# DMX-Controller.net
KiCad netlist of a schematic drawn in EAGLE
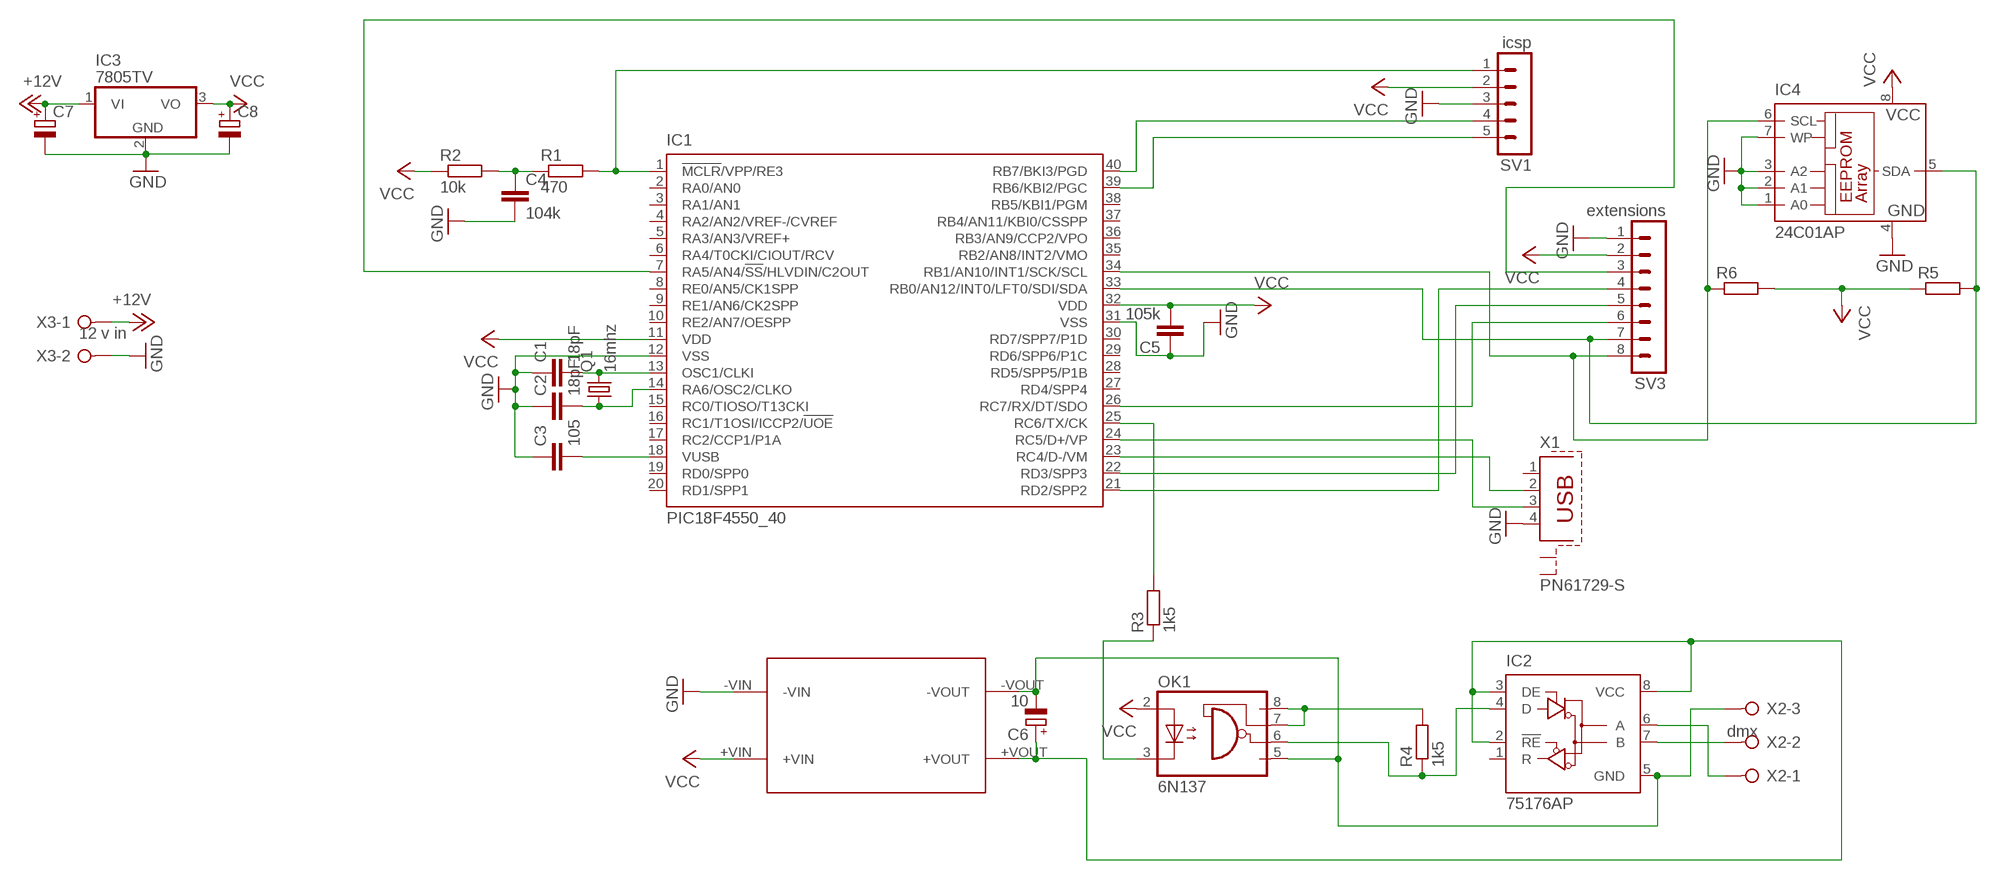
[diagram p0: schematic, sheet 1]

(export (version "E")
  (design (tool "Eeschema 10.0.6"))
  (components
    (comp (ref "C1")
      (value "18pF")
      (footprint "eagle-import:C050-024X044")
      (libsource (lib "eagle-import") (part "C-EU050-024X044"))
    )
    (comp (ref "C2")
      (value "18pF")
      (footprint "eagle-import:C050-024X044")
      (libsource (lib "eagle-import") (part "C-EU050-024X044"))
    )
    (comp (ref "C3")
      (value "105")
      (footprint "eagle-import:C050-024X044")
      (libsource (lib "eagle-import") (part "C-EU050-024X044"))
    )
    (comp (ref "C4")
      (value "104k")
      (footprint "eagle-import:C050-024X044")
      (libsource (lib "eagle-import") (part "C-EU050-024X044"))
    )
    (comp (ref "C5")
      (value "105k")
      (footprint "eagle-import:C050-024X044")
      (libsource (lib "eagle-import") (part "C-EU050-024X044"))
    )
    (comp (ref "C6")
      (value "10")
      (footprint "eagle-import:E2,5-6")
      (libsource (lib "eagle-import") (part "CPOL-EUE2.5-6"))
    )
    (comp (ref "C7")
      (value "CPOL-EUE2.5-6")
      (footprint "eagle-import:E2,5-6")
      (libsource (lib "eagle-import") (part "CPOL-EUE2.5-6"))
    )
    (comp (ref "C8")
      (value "CPOL-EUE2.5-6")
      (footprint "eagle-import:E2,5-6")
      (libsource (lib "eagle-import") (part "CPOL-EUE2.5-6"))
    )
    (comp (ref "IC1")
      (value "PIC18F4550_40")
      (footprint "eagle-import:DIL40")
      (fields (field (name "MF") "MICROCHIP") (field (name "MPN") "PIC18F4550-I/P"))
      (libsource (lib "eagle-import") (part "PIC18F4_40550"))
    )
    (comp (ref "IC2")
      (value "75176AP")
      (footprint "eagle-import:DIL08")
      (libsource (lib "eagle-import") (part "75176AP"))
    )
    (comp (ref "IC3")
      (value "7805TV")
      (footprint "eagle-import:TO220V")
      (libsource (lib "eagle-import") (part "78TV05"))
    )
    (comp (ref "IC4")
      (value "24C01AP")
      (footprint "eagle-import:DIL8")
      (fields (field (name "MF") "Arrow Electronics") (field (name "MPN") "M24C01-WBN6P"))
      (libsource (lib "eagle-import") (part "24CP01A"))
    )
    (comp (ref "OK1")
      (value "6N137")
      (footprint "eagle-import:DIL08")
      (libsource (lib "eagle-import") (part "6N137"))
    )
    (comp (ref "Q1")
      (value "16mhz")
      (footprint "eagle-import:HC49U-V")
      (libsource (lib "eagle-import") (part "CRYSTALHC49U-V"))
    )
    (comp (ref "R1")
      (value "470")
      (footprint "eagle-import:0207_10")
      (libsource (lib "eagle-import") (part "R-EU_0207/10"))
    )
    (comp (ref "R2")
      (value "10k")
      (footprint "eagle-import:0207_10")
      (libsource (lib "eagle-import") (part "R-EU_0207/10"))
    )
    (comp (ref "R3")
      (value "1k5")
      (footprint "eagle-import:0207_10")
      (libsource (lib "eagle-import") (part "R-EU_0207/10"))
    )
    (comp (ref "R4")
      (value "1k5")
      (footprint "eagle-import:0207_10")
      (libsource (lib "eagle-import") (part "R-EU_0207/10"))
    )
    (comp (ref "R5")
      (value "R-EU_0207/10")
      (footprint "eagle-import:0207_10")
      (libsource (lib "eagle-import") (part "R-EU_0207/10"))
    )
    (comp (ref "R6")
      (value "R-EU_0207/10")
      (footprint "eagle-import:0207_10")
      (libsource (lib "eagle-import") (part "R-EU_0207/10"))
    )
    (comp (ref "SV1")
      (value "icsp")
      (footprint "eagle-import:MA05-1")
      (libsource (lib "eagle-import") (part "MA05-1"))
    )
    (comp (ref "SV3")
      (value "extensions")
      (footprint "eagle-import:MA08-1")
      (libsource (lib "eagle-import") (part "MA08-1"))
    )
    (comp (ref "U$1")
      (value "SIM1-0505SZ")
      (footprint "eagle-import:SIM-0505SZ")
      (libsource (lib "eagle-import") (part "SIM1-0505SZ"))
    )
    (comp (ref "X1")
      (value "PN61729-S")
      (footprint "eagle-import:PN61729-S")
      (libsource (lib "eagle-import") (part "PN61729-S"))
    )
    (comp (ref "X2")
      (value "dmx")
      (footprint "eagle-import:W237-3E")
      (libsource (lib "eagle-import") (part "W237-3E"))
    )
    (comp (ref "X3")
      (value "12 v in")
      (footprint "eagle-import:W237-132")
      (libsource (lib "eagle-import") (part "W237-02P"))
    )
  )
  (nets
    (net (code "1") (name "+12V") (class "Default")
      (node (ref "C7") (pin "+") (pinfunction "+_+") (pintype "passive"))
      (node (ref "IC3") (pin "1") (pinfunction "VI_1") (pintype "input"))
      (node (ref "X3") (pin "1") (pinfunction "KL_1") (pintype "passive"))
    )
    (net (code "2") (name "GND") (class "Default")
      (node (ref "C1") (pin "1") (pinfunction "1_1") (pintype "passive"))
      (node (ref "C2") (pin "1") (pinfunction "1_1") (pintype "passive"))
      (node (ref "C3") (pin "1") (pinfunction "1_1") (pintype "passive"))
      (node (ref "C4") (pin "2") (pinfunction "2_2") (pintype "passive"))
      (node (ref "C5") (pin "1") (pinfunction "1_1") (pintype "passive"))
      (node (ref "C7") (pin "-") (pinfunction "-_-") (pintype "passive"))
      (node (ref "C8") (pin "-") (pinfunction "-_-") (pintype "passive"))
      (node (ref "IC1") (pin "12") (pinfunction "VSS_12") (pintype "power_in"))
      (node (ref "IC1") (pin "31") (pinfunction "VSS_31") (pintype "power_in"))
      (node (ref "IC3") (pin "2") (pinfunction "GND_2") (pintype "passive"))
      (node (ref "IC4") (pin "1") (pinfunction "A0_1") (pintype "input"))
      (node (ref "IC4") (pin "2") (pinfunction "A1_2") (pintype "input"))
      (node (ref "IC4") (pin "3") (pinfunction "A2_3") (pintype "input"))
      (node (ref "IC4") (pin "4") (pinfunction "GND_4") (pintype "power_in"))
      (node (ref "IC4") (pin "7") (pinfunction "WP_7") (pintype "input"))
      (node (ref "SV1") (pin "3") (pinfunction "3_3") (pintype "passive"))
      (node (ref "SV3") (pin "1") (pinfunction "1_1") (pintype "passive"))
      (node (ref "U$1") (pin "-VIN") (pinfunction "-VIN_-VIN") (pintype "input"))
      (node (ref "X1") (pin "4") (pinfunction "4_4") (pintype "passive"))
      (node (ref "X3") (pin "2") (pinfunction "KL_2") (pintype "passive"))
    )
    (net (code "3") (name "Net-(C4-Pad1)") (class "Default")
      (node (ref "C4") (pin "1") (pinfunction "1_1") (pintype "passive"))
      (node (ref "R1") (pin "1") (pinfunction "1_1") (pintype "passive"))
      (node (ref "R2") (pin "2") (pinfunction "2_2") (pintype "passive"))
    )
    (net (code "4") (name "Net-(IC1-OSC1{slash}CLKI)") (class "Default")
      (node (ref "C1") (pin "2") (pinfunction "2_2") (pintype "passive"))
      (node (ref "IC1") (pin "13") (pinfunction "OSC1/CLKI_13") (pintype "input"))
      (node (ref "Q1") (pin "2") (pinfunction "2_2") (pintype "passive"))
    )
    (net (code "5") (name "Net-(IC1-RA5{slash}AN4{slash}~{SS}{slash}HLVDIN{slash}C2OUT)") (class "Default")
      (node (ref "IC1") (pin "7") (pinfunction "RA5/AN4/~{SS}/HLVDIN/C2OUT_7") (pintype "bidirectional"))
      (node (ref "SV3") (pin "3") (pinfunction "3_3") (pintype "passive"))
    )
    (net (code "6") (name "Net-(IC1-RA6{slash}OSC2{slash}CLKO)") (class "Default")
      (node (ref "C2") (pin "2") (pinfunction "2_2") (pintype "passive"))
      (node (ref "IC1") (pin "14") (pinfunction "RA6/OSC2/CLKO_14") (pintype "output"))
      (node (ref "Q1") (pin "1") (pinfunction "1_1") (pintype "passive"))
    )
    (net (code "7") (name "Net-(IC1-RB0{slash}AN12{slash}INT0{slash}LFT0{slash}SDI{slash}SDA)") (class "Default")
      (node (ref "IC1") (pin "33") (pinfunction "RB0/AN12/INT0/LFT0/SDI/SDA_33") (pintype "bidirectional"))
      (node (ref "IC4") (pin "5") (pinfunction "SDA_5") (pintype "bidirectional"))
      (node (ref "R5") (pin "2") (pinfunction "2_2") (pintype "passive"))
      (node (ref "SV3") (pin "7") (pinfunction "7_7") (pintype "passive"))
    )
    (net (code "8") (name "Net-(IC1-RB1{slash}AN10{slash}INT1{slash}SCK{slash}SCL)") (class "Default")
      (node (ref "IC1") (pin "34") (pinfunction "RB1/AN10/INT1/SCK/SCL_34") (pintype "bidirectional"))
      (node (ref "IC4") (pin "6") (pinfunction "SCL_6") (pintype "input"))
      (node (ref "R6") (pin "1") (pinfunction "1_1") (pintype "passive"))
      (node (ref "SV3") (pin "8") (pinfunction "8_8") (pintype "passive"))
    )
    (net (code "9") (name "Net-(IC1-RB6{slash}KBI2{slash}PGC)") (class "Default")
      (node (ref "IC1") (pin "39") (pinfunction "RB6/KBI2/PGC_39") (pintype "bidirectional"))
      (node (ref "SV1") (pin "5") (pinfunction "5_5") (pintype "passive"))
    )
    (net (code "10") (name "Net-(IC1-RB7{slash}BKI3{slash}PGD)") (class "Default")
      (node (ref "IC1") (pin "40") (pinfunction "RB7/BKI3/PGD_40") (pintype "bidirectional"))
      (node (ref "SV1") (pin "4") (pinfunction "4_4") (pintype "passive"))
    )
    (net (code "11") (name "Net-(IC1-RC4{slash}D-{slash}VM)") (class "Default")
      (node (ref "IC1") (pin "23") (pinfunction "RC4/D-/VM_23") (pintype "bidirectional"))
      (node (ref "X1") (pin "2") (pinfunction "2_2") (pintype "passive"))
    )
    (net (code "12") (name "Net-(IC1-RC5{slash}D+{slash}VP)") (class "Default")
      (node (ref "IC1") (pin "24") (pinfunction "RC5/D+/VP_24") (pintype "bidirectional"))
      (node (ref "X1") (pin "3") (pinfunction "3_3") (pintype "passive"))
    )
    (net (code "13") (name "Net-(IC1-RC6{slash}TX{slash}CK)") (class "Default")
      (node (ref "IC1") (pin "25") (pinfunction "RC6/TX/CK_25") (pintype "bidirectional"))
      (node (ref "R3") (pin "2") (pinfunction "2_2") (pintype "passive"))
    )
    (net (code "14") (name "Net-(IC1-RC7{slash}RX{slash}DT{slash}SDO)") (class "Default")
      (node (ref "IC1") (pin "26") (pinfunction "RC7/RX/DT/SDO_26") (pintype "bidirectional"))
      (node (ref "SV3") (pin "6") (pinfunction "6_6") (pintype "passive"))
    )
    (net (code "15") (name "Net-(IC1-RD2{slash}SPP2)") (class "Default")
      (node (ref "IC1") (pin "21") (pinfunction "RD2/SPP2_21") (pintype "bidirectional"))
      (node (ref "SV3") (pin "4") (pinfunction "4_4") (pintype "passive"))
    )
    (net (code "16") (name "Net-(IC1-RD3{slash}SPP3)") (class "Default")
      (node (ref "IC1") (pin "22") (pinfunction "RD3/SPP3_22") (pintype "bidirectional"))
      (node (ref "SV3") (pin "5") (pinfunction "5_5") (pintype "passive"))
    )
    (net (code "17") (name "Net-(IC1-VUSB)") (class "Default")
      (node (ref "C3") (pin "2") (pinfunction "2_2") (pintype "passive"))
      (node (ref "IC1") (pin "18") (pinfunction "VUSB_18") (pintype "bidirectional"))
    )
    (net (code "18") (name "Net-(IC1-~{MCLR}{slash}VPP{slash}RE3)") (class "Default")
      (node (ref "IC1") (pin "1") (pinfunction "~{MCLR}/VPP/RE3_1") (pintype "input"))
      (node (ref "R1") (pin "2") (pinfunction "2_2") (pintype "passive"))
      (node (ref "SV1") (pin "1") (pinfunction "1_1") (pintype "passive"))
    )
    (net (code "19") (name "Net-(IC2-A)") (class "Default")
      (node (ref "IC2") (pin "6") (pinfunction "A_6") (pintype "output"))
      (node (ref "X2") (pin "1") (pinfunction "KL_1") (pintype "passive"))
    )
    (net (code "20") (name "Net-(IC2-B)") (class "Default")
      (node (ref "IC2") (pin "7") (pinfunction "B_7") (pintype "output"))
      (node (ref "X2") (pin "2") (pinfunction "KL_2") (pintype "passive"))
    )
    (net (code "21") (name "Net-(IC2-D)") (class "Default")
      (node (ref "IC2") (pin "4") (pinfunction "D_4") (pintype "input"))
      (node (ref "OK1") (pin "6") (pinfunction "VO_6") (pintype "passive"))
      (node (ref "R4") (pin "1") (pinfunction "1_1") (pintype "passive"))
    )
    (net (code "22") (name "Net-(IC2-DE)") (class "Default")
      (node (ref "C6") (pin "+") (pinfunction "+_+") (pintype "passive"))
      (node (ref "IC2") (pin "2") (pinfunction "~{RE}_2") (pintype "input"))
      (node (ref "IC2") (pin "3") (pinfunction "DE_3") (pintype "input"))
      (node (ref "IC2") (pin "8") (pinfunction "VCC_8") (pintype "power_in"))
      (node (ref "U$1") (pin "+VOUT") (pinfunction "+VOUT_+VOUT") (pintype "output"))
    )
    (net (code "23") (name "Net-(IC2-GND)") (class "Default")
      (node (ref "C6") (pin "-") (pinfunction "-_-") (pintype "passive"))
      (node (ref "IC2") (pin "5") (pinfunction "GND_5") (pintype "power_in"))
      (node (ref "OK1") (pin "5") (pinfunction "GND_5") (pintype "passive"))
      (node (ref "U$1") (pin "-VOUT") (pinfunction "-VOUT_-VOUT") (pintype "output"))
      (node (ref "X2") (pin "3") (pinfunction "KL_3") (pintype "passive"))
    )
    (net (code "24") (name "Net-(OK1-C)") (class "Default")
      (node (ref "OK1") (pin "3") (pinfunction "C_3") (pintype "passive"))
      (node (ref "R3") (pin "1") (pinfunction "1_1") (pintype "passive"))
    )
    (net (code "25") (name "Net-(OK1-VCC)") (class "Default")
      (node (ref "OK1") (pin "7") (pinfunction "VE_7") (pintype "passive"))
      (node (ref "OK1") (pin "8") (pinfunction "VCC_8") (pintype "passive"))
      (node (ref "R4") (pin "2") (pinfunction "2_2") (pintype "passive"))
    )
    (net (code "26") (name "VCC") (class "Default")
      (node (ref "C5") (pin "2") (pinfunction "2_2") (pintype "passive"))
      (node (ref "C8") (pin "+") (pinfunction "+_+") (pintype "passive"))
      (node (ref "IC1") (pin "11") (pinfunction "VDD_11") (pintype "power_in"))
      (node (ref "IC1") (pin "32") (pinfunction "VDD_32") (pintype "power_in"))
      (node (ref "IC3") (pin "3") (pinfunction "VO_3") (pintype "passive"))
      (node (ref "IC4") (pin "8") (pinfunction "VCC_8") (pintype "power_in"))
      (node (ref "OK1") (pin "2") (pinfunction "A_2") (pintype "passive"))
      (node (ref "R2") (pin "1") (pinfunction "1_1") (pintype "passive"))
      (node (ref "R5") (pin "1") (pinfunction "1_1") (pintype "passive"))
      (node (ref "R6") (pin "2") (pinfunction "2_2") (pintype "passive"))
      (node (ref "SV1") (pin "2") (pinfunction "2_2") (pintype "passive"))
      (node (ref "SV3") (pin "2") (pinfunction "2_2") (pintype "passive"))
      (node (ref "U$1") (pin "+VIN") (pinfunction "+VIN_+VIN") (pintype "input"))
    )
    (net (code "27") (name "unconnected-(IC1-RA0{slash}AN0-Pad2)") (class "Default")
      (node (ref "IC1") (pin "2") (pinfunction "RA0/AN0_2") (pintype "bidirectional"))
    )
    (net (code "28") (name "unconnected-(IC1-RA1{slash}AN1-Pad3)") (class "Default")
      (node (ref "IC1") (pin "3") (pinfunction "RA1/AN1_3") (pintype "bidirectional"))
    )
    (net (code "29") (name "unconnected-(IC1-RA2{slash}AN2{slash}VREF-{slash}CVREF-Pad4)") (class "Default")
      (node (ref "IC1") (pin "4") (pinfunction "RA2/AN2/VREF-/CVREF_4") (pintype "bidirectional"))
    )
    (net (code "30") (name "unconnected-(IC1-RA3{slash}AN3{slash}VREF+-Pad5)") (class "Default")
      (node (ref "IC1") (pin "5") (pinfunction "RA3/AN3/VREF+_5") (pintype "bidirectional"))
    )
    (net (code "31") (name "unconnected-(IC1-RA4{slash}T0CKI{slash}CIOUT{slash}RCV-Pad6)") (class "Default")
      (node (ref "IC1") (pin "6") (pinfunction "RA4/T0CKI/CIOUT/RCV_6") (pintype "bidirectional"))
    )
    (net (code "32") (name "unconnected-(IC1-RB2{slash}AN8{slash}INT2{slash}VMO-Pad35)") (class "Default")
      (node (ref "IC1") (pin "35") (pinfunction "RB2/AN8/INT2/VMO_35") (pintype "bidirectional"))
    )
    (net (code "33") (name "unconnected-(IC1-RB3{slash}AN9{slash}CCP2{slash}VPO-Pad36)") (class "Default")
      (node (ref "IC1") (pin "36") (pinfunction "RB3/AN9/CCP2/VPO_36") (pintype "bidirectional"))
    )
    (net (code "34") (name "unconnected-(IC1-RB4{slash}AN11{slash}KBI0{slash}CSSPP-Pad37)") (class "Default")
      (node (ref "IC1") (pin "37") (pinfunction "RB4/AN11/KBI0/CSSPP_37") (pintype "bidirectional"))
    )
    (net (code "35") (name "unconnected-(IC1-RB5{slash}KBI1{slash}PGM-Pad38)") (class "Default")
      (node (ref "IC1") (pin "38") (pinfunction "RB5/KBI1/PGM_38") (pintype "bidirectional"))
    )
    (net (code "36") (name "unconnected-(IC1-RC0{slash}TIOSO{slash}T13CKI-Pad15)") (class "Default")
      (node (ref "IC1") (pin "15") (pinfunction "RC0/TIOSO/T13CKI_15") (pintype "bidirectional"))
    )
    (net (code "37") (name "unconnected-(IC1-RC1{slash}T1OSI{slash}ICCP2{slash}~{UOE}-Pad16)") (class "Default")
      (node (ref "IC1") (pin "16") (pinfunction "RC1/T1OSI/ICCP2/~{UOE}_16") (pintype "bidirectional"))
    )
    (net (code "38") (name "unconnected-(IC1-RC2{slash}CCP1{slash}P1A-Pad17)") (class "Default")
      (node (ref "IC1") (pin "17") (pinfunction "RC2/CCP1/P1A_17") (pintype "bidirectional"))
    )
    (net (code "39") (name "unconnected-(IC1-RD0{slash}SPP0-Pad19)") (class "Default")
      (node (ref "IC1") (pin "19") (pinfunction "RD0/SPP0_19") (pintype "bidirectional"))
    )
    (net (code "40") (name "unconnected-(IC1-RD1{slash}SPP1-Pad20)") (class "Default")
      (node (ref "IC1") (pin "20") (pinfunction "RD1/SPP1_20") (pintype "bidirectional"))
    )
    (net (code "41") (name "unconnected-(IC1-RD4{slash}SPP4-Pad27)") (class "Default")
      (node (ref "IC1") (pin "27") (pinfunction "RD4/SPP4_27") (pintype "bidirectional"))
    )
    (net (code "42") (name "unconnected-(IC1-RD5{slash}SPP5{slash}P1B-Pad28)") (class "Default")
      (node (ref "IC1") (pin "28") (pinfunction "RD5/SPP5/P1B_28") (pintype "bidirectional"))
    )
    (net (code "43") (name "unconnected-(IC1-RD6{slash}SPP6{slash}P1C-Pad29)") (class "Default")
      (node (ref "IC1") (pin "29") (pinfunction "RD6/SPP6/P1C_29") (pintype "bidirectional"))
    )
    (net (code "44") (name "unconnected-(IC1-RD7{slash}SPP7{slash}P1D-Pad30)") (class "Default")
      (node (ref "IC1") (pin "30") (pinfunction "RD7/SPP7/P1D_30") (pintype "bidirectional"))
    )
    (net (code "45") (name "unconnected-(IC1-RE0{slash}AN5{slash}CK1SPP-Pad8)") (class "Default")
      (node (ref "IC1") (pin "8") (pinfunction "RE0/AN5/CK1SPP_8") (pintype "bidirectional"))
    )
    (net (code "46") (name "unconnected-(IC1-RE1{slash}AN6{slash}CK2SPP-Pad9)") (class "Default")
      (node (ref "IC1") (pin "9") (pinfunction "RE1/AN6/CK2SPP_9") (pintype "bidirectional"))
    )
    (net (code "47") (name "unconnected-(IC1-RE2{slash}AN7{slash}OESPP-Pad10)") (class "Default")
      (node (ref "IC1") (pin "10") (pinfunction "RE2/AN7/OESPP_10") (pintype "bidirectional"))
    )
    (net (code "48") (name "unconnected-(IC2-R-Pad1)") (class "Default")
      (node (ref "IC2") (pin "1") (pinfunction "R_1") (pintype "input"))
    )
    (net (code "49") (name "unconnected-(X1-Pad1)") (class "Default")
      (node (ref "X1") (pin "1") (pinfunction "1_1") (pintype "passive"))
    )
    (net (code "50") (name "unconnected-(X1-PadS1)") (class "Default")
      (node (ref "X1") (pin "S1") (pinfunction "S1_S1") (pintype "passive"))
    )
    (net (code "51") (name "unconnected-(X1-PadS2)") (class "Default")
      (node (ref "X1") (pin "S2") (pinfunction "S2_S2") (pintype "passive"))
    )
  )
)
